# CurrentProbe.net
KiCad netlist of a schematic drawn in Altium Designer
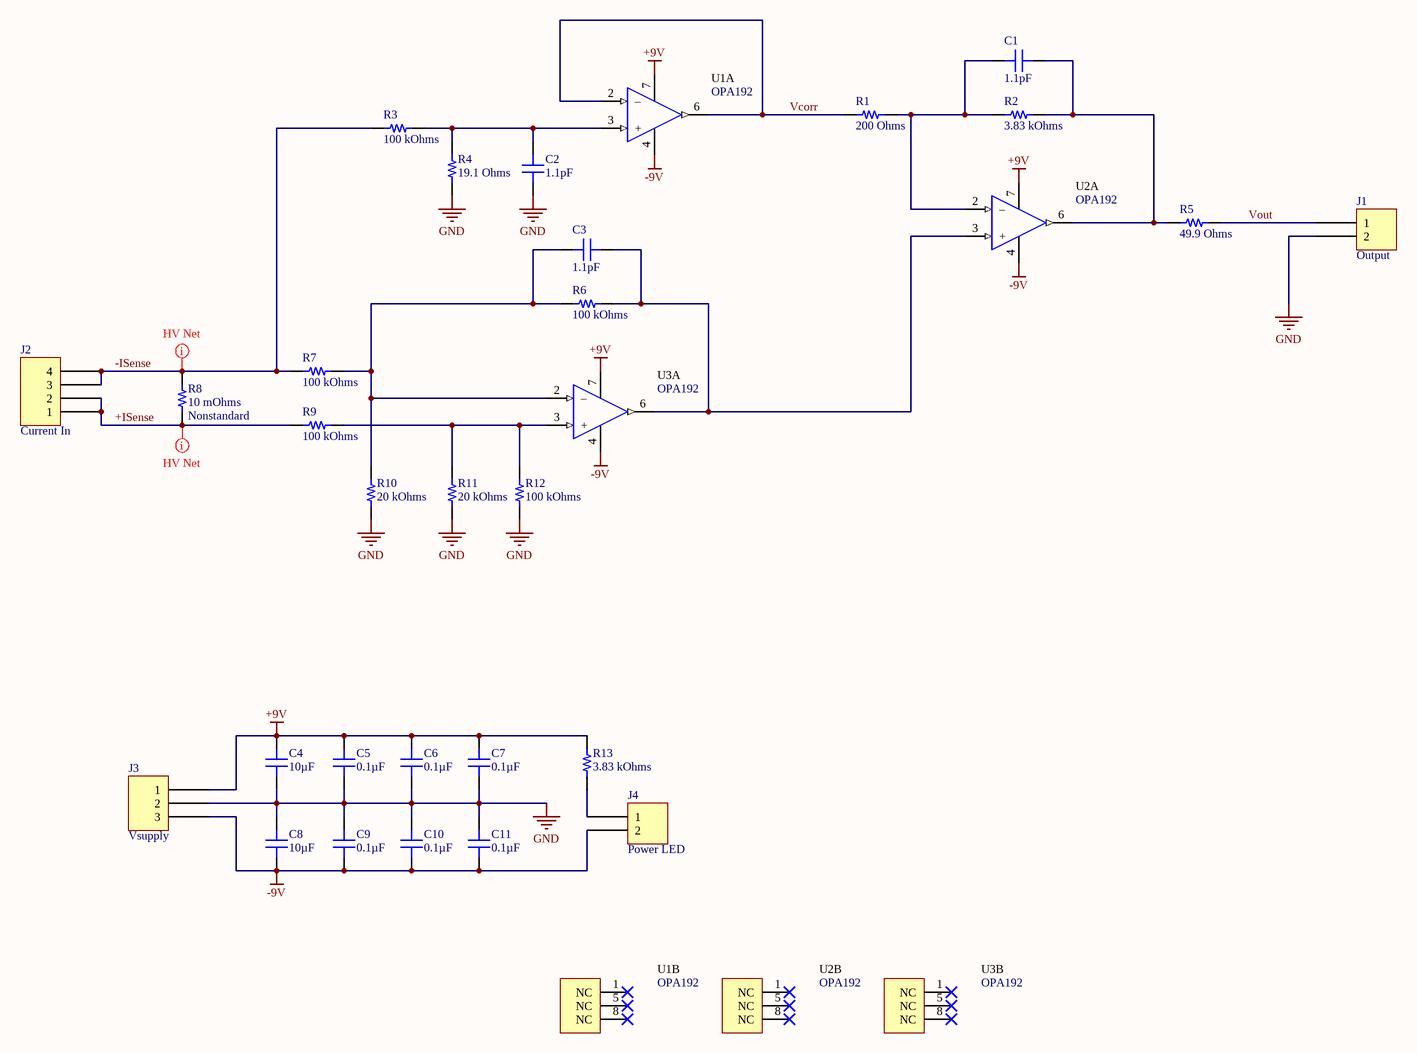
[diagram p0: CurrentProbe.SchDoc]

(export (version "E")
  (design (tool "Eeschema 10.0.6"))
  (components
    (comp (ref "C1")
      (value "1.1pF")
      (footprint "CAP 0805_2012")
      (description "CAP CER 1.1PF 250V C0G/NP0 0805")
      (fields
        (field (name "PART NUMBER") "600F1R1BT250XT")
        (field (name "MANUFACTURER") "American Technical Ceramics")
      )
      (libsource (lib "Celestial Altium Library - altium_library") (part "Capacitor"))
    )
    (comp (ref "C2")
      (value "1.1pF")
      (footprint "CAP 0805_2012")
      (description "CAP CER 1.1PF 250V C0G/NP0 0805")
      (fields
        (field (name "PART NUMBER") "600F1R1BT250XT")
        (field (name "MANUFACTURER") "American Technical Ceramics")
      )
      (libsource (lib "Celestial Altium Library - altium_library") (part "Capacitor"))
    )
    (comp (ref "C3")
      (value "1.1pF")
      (footprint "CAP 0805_2012")
      (description "CAP CER 1.1PF 250V C0G/NP0 0805")
      (fields
        (field (name "PART NUMBER") "600F1R1BT250XT")
        (field (name "MANUFACTURER") "American Technical Ceramics")
      )
      (libsource (lib "Celestial Altium Library - altium_library") (part "Capacitor"))
    )
    (comp (ref "C4")
      (value "10µF")
      (footprint "CAP 0805_2012")
      (description "CAP CER 10UF 25V X5R 0805")
      (fields
        (field (name "PART NUMBER") "CL21A106KAYNNNE")
        (field (name "MANUFACTURER") "Samsung Electro-Mechanics")
      )
      (libsource (lib "Celestial Altium Library - altium_library") (part "Capacitor"))
    )
    (comp (ref "C5")
      (value "0.1µF")
      (footprint "CAP 0805_2012")
      (description "CAP CER 0.1UF 25V X7R 0805")
      (fields (field (name "PART NUMBER") "CC0805MRX7R8BB104") (field (name "MANUFACTURER") "Yageo"))
      (libsource (lib "Celestial Altium Library - altium_library") (part "Capacitor"))
    )
    (comp (ref "C6")
      (value "0.1µF")
      (footprint "CAP 0805_2012")
      (description "CAP CER 0.1UF 25V X7R 0805")
      (fields (field (name "PART NUMBER") "CC0805MRX7R8BB104") (field (name "MANUFACTURER") "Yageo"))
      (libsource (lib "Celestial Altium Library - altium_library") (part "Capacitor"))
    )
    (comp (ref "C7")
      (value "0.1µF")
      (footprint "CAP 0805_2012")
      (description "CAP CER 0.1UF 25V X7R 0805")
      (fields (field (name "PART NUMBER") "CC0805MRX7R8BB104") (field (name "MANUFACTURER") "Yageo"))
      (libsource (lib "Celestial Altium Library - altium_library") (part "Capacitor"))
    )
    (comp (ref "C8")
      (value "10µF")
      (footprint "CAP 0805_2012")
      (description "CAP CER 10UF 25V X5R 0805")
      (fields
        (field (name "PART NUMBER") "CL21A106KAYNNNE")
        (field (name "MANUFACTURER") "Samsung Electro-Mechanics")
      )
      (libsource (lib "Celestial Altium Library - altium_library") (part "Capacitor"))
    )
    (comp (ref "C9")
      (value "0.1µF")
      (footprint "CAP 0805_2012")
      (description "CAP CER 0.1UF 25V X7R 0805")
      (fields (field (name "PART NUMBER") "CC0805MRX7R8BB104") (field (name "MANUFACTURER") "Yageo"))
      (libsource (lib "Celestial Altium Library - altium_library") (part "Capacitor"))
    )
    (comp (ref "C10")
      (value "0.1µF")
      (footprint "CAP 0805_2012")
      (description "CAP CER 0.1UF 25V X7R 0805")
      (fields (field (name "PART NUMBER") "CC0805MRX7R8BB104") (field (name "MANUFACTURER") "Yageo"))
      (libsource (lib "Celestial Altium Library - altium_library") (part "Capacitor"))
    )
    (comp (ref "C11")
      (value "0.1µF")
      (footprint "CAP 0805_2012")
      (description "CAP CER 0.1UF 25V X7R 0805")
      (fields (field (name "PART NUMBER") "CC0805MRX7R8BB104") (field (name "MANUFACTURER") "Yageo"))
      (libsource (lib "Celestial Altium Library - altium_library") (part "Capacitor"))
    )
    (comp (ref "J1")
      (value "Output")
      (footprint "MOLEX KK 0022272021")
      (description "CONN HEADER VERT 2POS 2.54MM")
      (fields (field (name "PART NUMBER") "0022272021") (field (name "MANUFACTURER") "Molex"))
      (libsource (lib "Celestial Altium Library - altium_library") (part "2 Pin"))
    )
    (comp (ref "J2")
      (value "Current In")
      (footprint "TE 282834-4")
      (description "TERM BLK 4P SIDE ENT 2.54MM PCB")
      (fields
        (field (name "PART NUMBER") "282834-4")
        (field (name "MANUFACTURER") "TE Connectivity AMP Connectors")
      )
      (libsource (lib "Celestial Altium Library - altium_library") (part "4 Pin"))
    )
    (comp (ref "J3")
      (value "Vsupply")
      (footprint "MOLEX KK 0022272031")
      (description "CONN HEADER VERT 3POS 2.54MM")
      (fields (field (name "PART NUMBER") "0022272031") (field (name "MANUFACTURER") "Molex"))
      (libsource (lib "Celestial Altium Library - altium_library") (part "3 Pin"))
    )
    (comp (ref "J4")
      (value "Power LED")
      (footprint "MOLEX KK 0022272021")
      (description "CONN HEADER VERT 2POS 2.54MM")
      (fields (field (name "PART NUMBER") "0022272021") (field (name "MANUFACTURER") "Molex"))
      (libsource (lib "Celestial Altium Library - altium_library") (part "2 Pin"))
    )
    (comp (ref "R1")
      (value "200 Ohms")
      (footprint "RES 0805_2012")
      (description "RES SMD 200 OHM 0.1% 1/4W 0805")
      (fields
        (field (name "PART NUMBER") "ERJ-PB6B2000V")
        (field (name "MANUFACTURER") "Panasonic Electronic Components")
      )
      (libsource (lib "Celestial Altium Library - altium_library") (part "Resistor"))
    )
    (comp (ref "R2")
      (value "3.83 kOhms")
      (footprint "RES 0805_2012")
      (description "RES SMD 3.83K OHM 0.5% 1/4W 0805")
      (fields
        (field (name "PART NUMBER") "ERJ-PB6D3831V")
        (field (name "MANUFACTURER") "Panasonic Electronic Components")
      )
      (libsource (lib "Celestial Altium Library - altium_library") (part "Resistor"))
    )
    (comp (ref "R3")
      (value "100 kOhms")
      (footprint "RES 0805_2012")
      (description "RES 100K OHM 0.1% 1/8W 0805")
      (fields
        (field (name "PART NUMBER") "ERA-6AEB104V")
        (field (name "MANUFACTURER") "Panasonic Electronic Components")
      )
      (libsource (lib "Celestial Altium Library - altium_library") (part "Resistor"))
    )
    (comp (ref "R4")
      (value "19.1 Ohms")
      (footprint "RES 0805_2012")
      (description "RES SMD 19.1 OHM 0.1% 1/4W 0805")
      (fields
        (field (name "PART NUMBER") "5-1625868-4")
        (field (name "MANUFACTURER") "TE Connectivity Passive Product")
      )
      (libsource (lib "Celestial Altium Library - altium_library") (part "Resistor"))
    )
    (comp (ref "R5")
      (value "49.9 Ohms")
      (footprint "RES 0805_2012")
      (description "RES SMD 49.9 OHM 1% 1/8W 0805")
      (fields
        (field (name "PART NUMBER") "ERJ-6ENF49R9V")
        (field (name "MANUFACTURER") "Panasonic Electronic Components")
      )
      (libsource (lib "Celestial Altium Library - altium_library") (part "Resistor"))
    )
    (comp (ref "R6")
      (value "100 kOhms")
      (footprint "RES 0805_2012")
      (description "RES 100K OHM 0.1% 1/8W 0805")
      (fields
        (field (name "PART NUMBER") "ERA-6AEB104V")
        (field (name "MANUFACTURER") "Panasonic Electronic Components")
      )
      (libsource (lib "Celestial Altium Library - altium_library") (part "Resistor"))
    )
    (comp (ref "R7")
      (value "100 kOhms")
      (footprint "RES 0805_2012")
      (description "RES 100K OHM 0.1% 1/8W 0805")
      (fields
        (field (name "PART NUMBER") "ERA-6AEB104V")
        (field (name "MANUFACTURER") "Panasonic Electronic Components")
      )
      (libsource (lib "Celestial Altium Library - altium_library") (part "Resistor"))
    )
    (comp (ref "R8")
      (value "10 mOhms")
      (footprint "VISHAY WSHP2818")
      (description "RES 0.01 OHM 1% 10W 2818")
      (fields
        (field (name "PART NUMBER") "WSHP2818R0100FEA")
        (field (name "PACKAGE / CASE") "Nonstandard")
        (field (name "MANUFACTURER") "Vishay Dale")
      )
      (libsource (lib "Celestial Altium Library - altium_library") (part "Resistor"))
    )
    (comp (ref "R9")
      (value "100 kOhms")
      (footprint "RES 0805_2012")
      (description "RES 100K OHM 0.1% 1/8W 0805")
      (fields
        (field (name "PART NUMBER") "ERA-6AEB104V")
        (field (name "MANUFACTURER") "Panasonic Electronic Components")
      )
      (libsource (lib "Celestial Altium Library - altium_library") (part "Resistor"))
    )
    (comp (ref "R10")
      (value "20 kOhms")
      (footprint "RES 0805_2012")
      (description "RES 20K OHM 0.05% 1/8W 0805")
      (fields
        (field (name "PART NUMBER") "ERA-6ARW203V")
        (field (name "MANUFACTURER") "Panasonic Electronic Components")
      )
      (libsource (lib "Celestial Altium Library - altium_library") (part "Resistor"))
    )
    (comp (ref "R11")
      (value "20 kOhms")
      (footprint "RES 0805_2012")
      (description "RES 20K OHM 0.05% 1/8W 0805")
      (fields
        (field (name "PART NUMBER") "ERA-6ARW203V")
        (field (name "MANUFACTURER") "Panasonic Electronic Components")
      )
      (libsource (lib "Celestial Altium Library - altium_library") (part "Resistor"))
    )
    (comp (ref "R12")
      (value "100 kOhms")
      (footprint "RES 0805_2012")
      (description "RES 100K OHM 0.1% 1/8W 0805")
      (fields
        (field (name "PART NUMBER") "ERA-6AEB104V")
        (field (name "MANUFACTURER") "Panasonic Electronic Components")
      )
      (libsource (lib "Celestial Altium Library - altium_library") (part "Resistor"))
    )
    (comp (ref "R13")
      (value "3.83 kOhms")
      (footprint "RES 0805_2012")
      (description "RES SMD 3.83K OHM 0.5% 1/4W 0805")
      (fields
        (field (name "PART NUMBER") "ERJ-PB6D3831V")
        (field (name "MANUFACTURER") "Panasonic Electronic Components")
      )
      (libsource (lib "Celestial Altium Library - altium_library") (part "Resistor"))
    )
    (comp (ref "U1")
      (value "OPA192")
      (footprint "SOIC127P600X175-8N")
      (description "Precision, Rail to Rail I/O, Low Vos, Low Ib Op Amp")
      (fields (field (name "MANUFACTURER") "Texas Instruments") (field (name "DESIGNER") "Alex Davis"))
      (libsource (lib "TI_Misc") (part "OPA192ID"))
    )
    (comp (ref "U2")
      (value "OPA192")
      (footprint "SOIC127P600X175-8N")
      (description "Precision, Rail to Rail I/O, Low Vos, Low Ib Op Amp")
      (fields (field (name "MANUFACTURER") "Texas Instruments") (field (name "DESIGNER") "Alex Davis"))
      (libsource (lib "TI_Misc") (part "OPA192ID"))
    )
    (comp (ref "U3")
      (value "OPA192")
      (footprint "SOIC127P600X175-8N")
      (description "Precision, Rail to Rail I/O, Low Vos, Low Ib Op Amp")
      (fields (field (name "MANUFACTURER") "Texas Instruments") (field (name "DESIGNER") "Alex Davis"))
      (libsource (lib "TI_Misc") (part "OPA192ID"))
    )
  )
  (nets
    (net (code "1") (name "+9V") (class "Default")
      (node (ref "C4") (pin "2") (pinfunction "2_2") (pintype "passive"))
      (node (ref "C5") (pin "1") (pinfunction "1_1") (pintype "passive"))
      (node (ref "C6") (pin "1") (pinfunction "1_1") (pintype "passive"))
      (node (ref "C7") (pin "1") (pinfunction "1_1") (pintype "passive"))
      (node (ref "J3") (pin "1") (pinfunction "1_1") (pintype "passive"))
      (node (ref "R13") (pin "2") (pinfunction "2_2") (pintype "passive"))
      (node (ref "U1") (pin "7") (pinfunction "V+_7") (pintype "power_in"))
      (node (ref "U2") (pin "7") (pinfunction "V+_7") (pintype "power_in"))
      (node (ref "U3") (pin "7") (pinfunction "V+_7") (pintype "power_in"))
    )
    (net (code "2") (name "-9V") (class "Default")
      (node (ref "C10") (pin "2") (pinfunction "2_2") (pintype "passive"))
      (node (ref "C11") (pin "2") (pinfunction "2_2") (pintype "passive"))
      (node (ref "C8") (pin "1") (pinfunction "1_1") (pintype "passive"))
      (node (ref "C9") (pin "2") (pinfunction "2_2") (pintype "passive"))
      (node (ref "J3") (pin "3") (pinfunction "3_3") (pintype "passive"))
      (node (ref "J4") (pin "2") (pinfunction "2_2") (pintype "passive"))
      (node (ref "U1") (pin "4") (pinfunction "V-_4") (pintype "power_in"))
      (node (ref "U2") (pin "4") (pinfunction "V-_4") (pintype "power_in"))
      (node (ref "U3") (pin "4") (pinfunction "V-_4") (pintype "power_in"))
    )
    (net (code "3") (name "/+ISense") (class "Default")
      (node (ref "J2") (pin "1") (pinfunction "1_1") (pintype "passive"))
      (node (ref "J2") (pin "2") (pinfunction "2_2") (pintype "passive"))
      (node (ref "R8") (pin "1") (pinfunction "1_1") (pintype "passive"))
      (node (ref "R9") (pin "1") (pinfunction "1_1") (pintype "passive"))
    )
    (net (code "4") (name "/-ISense") (class "Default")
      (node (ref "J2") (pin "3") (pinfunction "3_3") (pintype "passive"))
      (node (ref "J2") (pin "4") (pinfunction "4_4") (pintype "passive"))
      (node (ref "R3") (pin "1") (pinfunction "1_1") (pintype "passive"))
      (node (ref "R7") (pin "1") (pinfunction "1_1") (pintype "passive"))
      (node (ref "R8") (pin "2") (pinfunction "2_2") (pintype "passive"))
    )
    (net (code "5") (name "/Vcorr") (class "Default")
      (node (ref "R1") (pin "1") (pinfunction "1_1") (pintype "passive"))
      (node (ref "U1") (pin "2") (pinfunction "–_2") (pintype "input"))
      (node (ref "U1") (pin "6") (pinfunction "Out_6") (pintype "output"))
    )
    (net (code "6") (name "/Vout") (class "Default")
      (node (ref "J1") (pin "1") (pinfunction "1_1") (pintype "passive"))
      (node (ref "R5") (pin "2") (pinfunction "2_2") (pintype "passive"))
    )
    (net (code "7") (name "GND") (class "Default")
      (node (ref "C10") (pin "1") (pinfunction "1_1") (pintype "passive"))
      (node (ref "C11") (pin "1") (pinfunction "1_1") (pintype "passive"))
      (node (ref "C2") (pin "2") (pinfunction "2_2") (pintype "passive"))
      (node (ref "C4") (pin "1") (pinfunction "1_1") (pintype "passive"))
      (node (ref "C5") (pin "2") (pinfunction "2_2") (pintype "passive"))
      (node (ref "C6") (pin "2") (pinfunction "2_2") (pintype "passive"))
      (node (ref "C7") (pin "2") (pinfunction "2_2") (pintype "passive"))
      (node (ref "C8") (pin "2") (pinfunction "2_2") (pintype "passive"))
      (node (ref "C9") (pin "1") (pinfunction "1_1") (pintype "passive"))
      (node (ref "J1") (pin "2") (pinfunction "2_2") (pintype "passive"))
      (node (ref "J3") (pin "2") (pinfunction "2_2") (pintype "passive"))
      (node (ref "R10") (pin "1") (pinfunction "1_1") (pintype "passive"))
      (node (ref "R11") (pin "1") (pinfunction "1_1") (pintype "passive"))
      (node (ref "R12") (pin "1") (pinfunction "1_1") (pintype "passive"))
      (node (ref "R4") (pin "1") (pinfunction "1_1") (pintype "passive"))
    )
    (net (code "8") (name "Net-(J4-Pad1)") (class "Default")
      (node (ref "J4") (pin "1") (pinfunction "1_1") (pintype "passive"))
      (node (ref "R13") (pin "1") (pinfunction "1_1") (pintype "passive"))
    )
    (net (code "9") (name "Net-(U1A-+)") (class "Default")
      (node (ref "C2") (pin "1") (pinfunction "1_1") (pintype "passive"))
      (node (ref "R3") (pin "2") (pinfunction "2_2") (pintype "passive"))
      (node (ref "R4") (pin "2") (pinfunction "2_2") (pintype "passive"))
      (node (ref "U1") (pin "3") (pinfunction "+_3") (pintype "input"))
    )
    (net (code "10") (name "Net-(U2A-+)") (class "Default")
      (node (ref "C3") (pin "2") (pinfunction "2_2") (pintype "passive"))
      (node (ref "R6") (pin "2") (pinfunction "2_2") (pintype "passive"))
      (node (ref "U2") (pin "3") (pinfunction "+_3") (pintype "input"))
      (node (ref "U3") (pin "6") (pinfunction "Out_6") (pintype "output"))
    )
    (net (code "11") (name "Net-(U2A-Out)") (class "Default")
      (node (ref "C1") (pin "2") (pinfunction "2_2") (pintype "passive"))
      (node (ref "R2") (pin "2") (pinfunction "2_2") (pintype "passive"))
      (node (ref "R5") (pin "1") (pinfunction "1_1") (pintype "passive"))
      (node (ref "U2") (pin "6") (pinfunction "Out_6") (pintype "output"))
    )
    (net (code "12") (name "Net-(U2A-–)") (class "Default")
      (node (ref "C1") (pin "1") (pinfunction "1_1") (pintype "passive"))
      (node (ref "R1") (pin "2") (pinfunction "2_2") (pintype "passive"))
      (node (ref "R2") (pin "1") (pinfunction "1_1") (pintype "passive"))
      (node (ref "U2") (pin "2") (pinfunction "–_2") (pintype "input"))
    )
    (net (code "13") (name "Net-(U3A-+)") (class "Default")
      (node (ref "R11") (pin "2") (pinfunction "2_2") (pintype "passive"))
      (node (ref "R12") (pin "2") (pinfunction "2_2") (pintype "passive"))
      (node (ref "R9") (pin "2") (pinfunction "2_2") (pintype "passive"))
      (node (ref "U3") (pin "3") (pinfunction "+_3") (pintype "input"))
    )
    (net (code "14") (name "Net-(U3A-–)") (class "Default")
      (node (ref "C3") (pin "1") (pinfunction "1_1") (pintype "passive"))
      (node (ref "R10") (pin "2") (pinfunction "2_2") (pintype "passive"))
      (node (ref "R6") (pin "1") (pinfunction "1_1") (pintype "passive"))
      (node (ref "R7") (pin "2") (pinfunction "2_2") (pintype "passive"))
      (node (ref "U3") (pin "2") (pinfunction "–_2") (pintype "input"))
    )
    (net (code "15") (name "unconnected-(U1B-NC-Pad1)") (class "Default")
      (node (ref "U1") (pin "1") (pinfunction "NC_1") (pintype "passive+no_connect"))
    )
    (net (code "16") (name "unconnected-(U1B-NC-Pad5)") (class "Default")
      (node (ref "U1") (pin "5") (pinfunction "NC_5") (pintype "passive+no_connect"))
    )
    (net (code "17") (name "unconnected-(U1B-NC-Pad8)") (class "Default")
      (node (ref "U1") (pin "8") (pinfunction "NC_8") (pintype "passive+no_connect"))
    )
    (net (code "18") (name "unconnected-(U2B-NC-Pad1)") (class "Default")
      (node (ref "U2") (pin "1") (pinfunction "NC_1") (pintype "passive+no_connect"))
    )
    (net (code "19") (name "unconnected-(U2B-NC-Pad5)") (class "Default")
      (node (ref "U2") (pin "5") (pinfunction "NC_5") (pintype "passive+no_connect"))
    )
    (net (code "20") (name "unconnected-(U2B-NC-Pad8)") (class "Default")
      (node (ref "U2") (pin "8") (pinfunction "NC_8") (pintype "passive+no_connect"))
    )
    (net (code "21") (name "unconnected-(U3B-NC-Pad1)") (class "Default")
      (node (ref "U3") (pin "1") (pinfunction "NC_1") (pintype "passive+no_connect"))
    )
    (net (code "22") (name "unconnected-(U3B-NC-Pad5)") (class "Default")
      (node (ref "U3") (pin "5") (pinfunction "NC_5") (pintype "passive+no_connect"))
    )
    (net (code "23") (name "unconnected-(U3B-NC-Pad8)") (class "Default")
      (node (ref "U3") (pin "8") (pinfunction "NC_8") (pintype "passive+no_connect"))
    )
  )
)
